# MCU089B_XDS110_USB_Power.net
KiCad netlist of a schematic drawn in Altium Designer
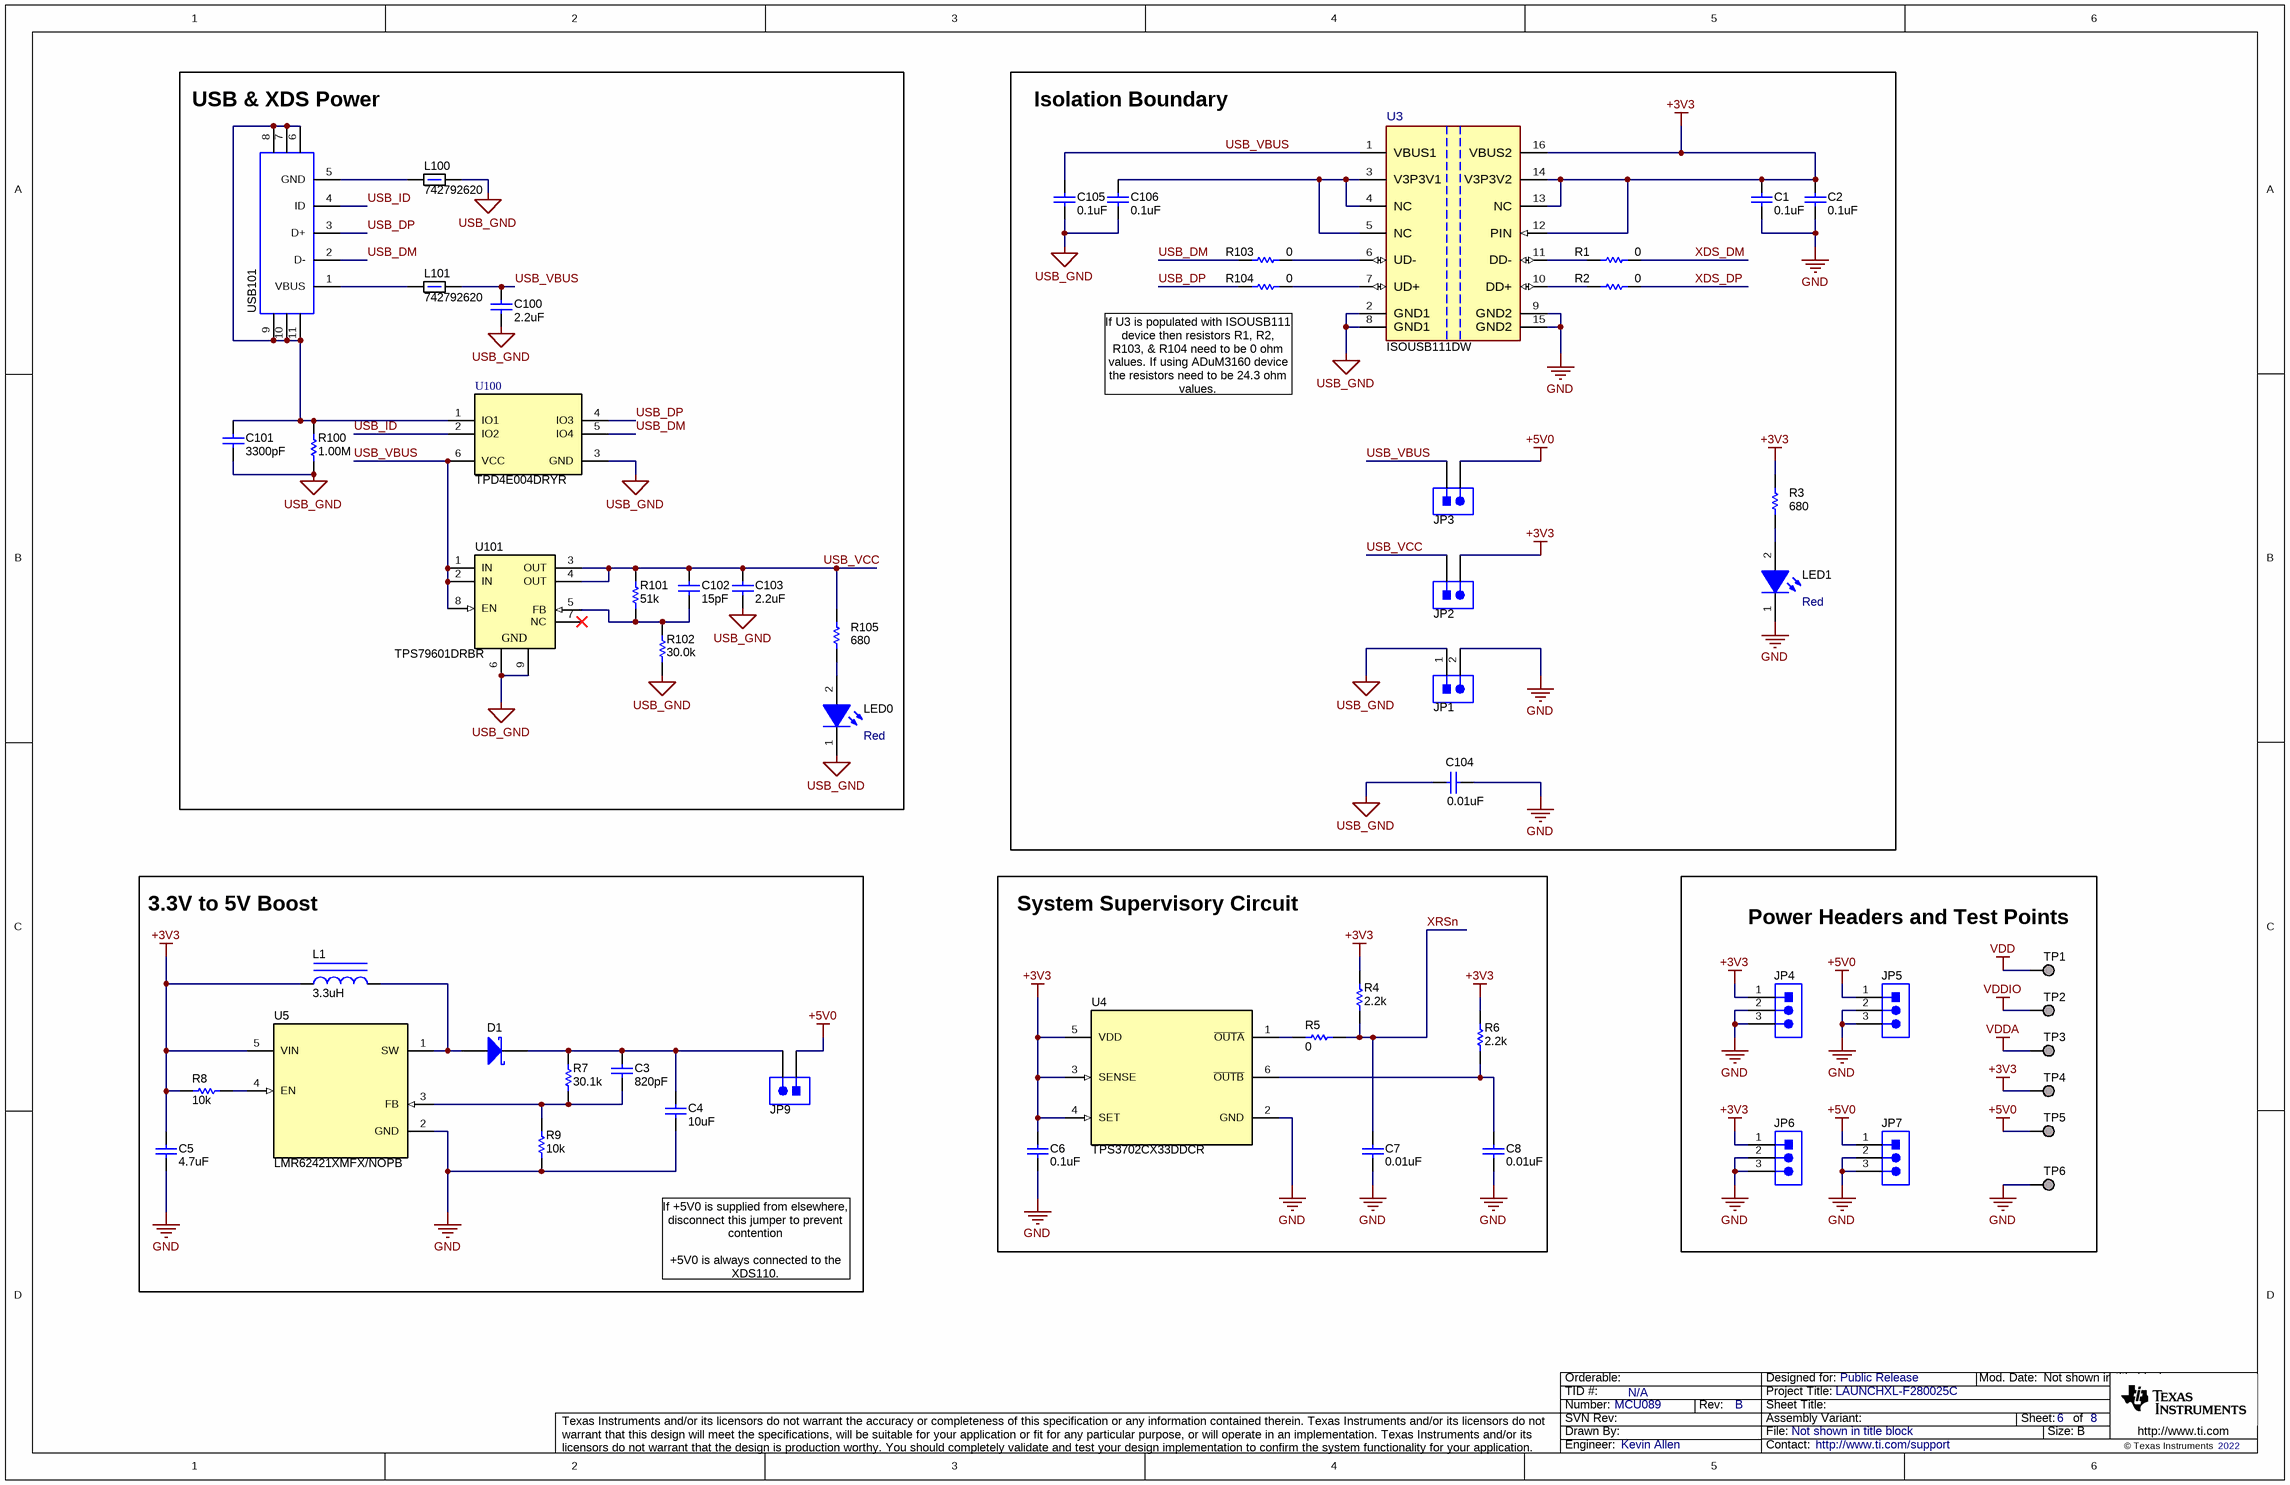
[diagram p0: MCU089B_XDS110_USB_Power.SchDoc]

(export (version "E")
  (design (tool "Eeschema 10.0.6"))
  (components
    (comp (ref "C1")
      (value "GRM155R71A104KA01D")
      (footprint "0402")
      (description "CAP, CERM, 0.1 uF, 10 V, +/- 10%, X7R, 0402")
      (fields
        (field (name "VALUEDISPLAYED") "0.1uF")
        (field (name "MANUFACTURER") "MuRata")
        (field (name "PUBLISHER") "Texas Instruments")
      )
      (libsource (lib "Altium Vault - TI") (part "Capacitor"))
    )
    (comp (ref "C2")
      (value "GRM155R71A104KA01D")
      (footprint "0402")
      (description "CAP, CERM, 0.1 uF, 10 V, +/- 10%, X7R, 0402")
      (fields
        (field (name "VALUEDISPLAYED") "0.1uF")
        (field (name "MANUFACTURER") "MuRata")
        (field (name "PUBLISHER") "Texas Instruments")
      )
      (libsource (lib "Altium Vault - TI") (part "Capacitor"))
    )
    (comp (ref "C3")
      (value "GRM1555C1E821JA01D")
      (footprint "0402")
      (description "CAP, CERM, 820 pF, 25 V, +/- 5%, C0G/NP0, 0402")
      (fields
        (field (name "MANUFACTURER") "MuRata")
        (field (name "VALUEDISPLAYED") "820pF")
        (field (name "PUBLISHER") "Texas Instruments")
      )
      (libsource (lib "Altium Vault - TI") (part "Capacitor"))
    )
    (comp (ref "C4")
      (value "885012209028")
      (footprint "1210_220")
      (description "CAP, CERM, 10 uF, 25 V,+/- 10%, X7R, 1210")
      (fields
        (field (name "VALUEDISPLAYED") "10uF")
        (field (name "MANUFACTURER") "Wurth Elektronik")
        (field (name "PUBLISHER") "Texas Instruments")
      )
      (libsource (lib "Altium Vault - TI") (part "Capacitor"))
    )
    (comp (ref "C5")
      (value "885012105008")
      (footprint "0402")
      (description "CAP, CERM, 4.7 uF, 6.3 V, +/- 20%, X5R, 0402")
      (fields
        (field (name "VALUEDISPLAYED") "4.7uF")
        (field (name "MANUFACTURER") "Wurth Elektronik")
        (field (name "PUBLISHER") "Texas Instruments")
      )
      (libsource (lib "Altium Vault - TI") (part "Capacitor"))
    )
    (comp (ref "C6")
      (value "GRM155R71A104KA01D")
      (footprint "0402")
      (description "CAP, CERM, 0.1 uF, 10 V, +/- 10%, X7R, 0402")
      (fields
        (field (name "VALUEDISPLAYED") "0.1uF")
        (field (name "MANUFACTURER") "MuRata")
        (field (name "PUBLISHER") "Texas Instruments")
      )
      (libsource (lib "Altium Vault - TI") (part "Capacitor"))
    )
    (comp (ref "C7")
      (value "GRM155R71E103KA01D")
      (footprint "0402")
      (description "CAP, CERM, 0.01 uF, 25 V, +/- 10%, X7R, 0402")
      (fields
        (field (name "VALUEDISPLAYED") "0.01uF")
        (field (name "MANUFACTURER") "MuRata")
        (field (name "PUBLISHER") "Texas Instruments")
      )
      (libsource (lib "Altium Vault - TI") (part "Capacitor"))
    )
    (comp (ref "C8")
      (value "GRM155R71E103KA01D")
      (footprint "0402")
      (description "CAP, CERM, 0.01 uF, 25 V, +/- 10%, X7R, 0402")
      (fields
        (field (name "VALUEDISPLAYED") "0.01uF")
        (field (name "MANUFACTURER") "MuRata")
        (field (name "PUBLISHER") "Texas Instruments")
      )
      (libsource (lib "Altium Vault - TI") (part "Capacitor"))
    )
    (comp (ref "C100")
      (value "GRM155R60J225KE95D")
      (footprint "0402")
      (description "CAP, CERM, 2.2 uF, 6.3 V, +/- 10%, X5R, 0402")
      (fields
        (field (name "VALUEDISPLAYED") "2.2uF")
        (field (name "MANUFACTURER") "MuRata")
        (field (name "PUBLISHER") "Texas Instruments")
      )
      (libsource (lib "Altium Vault - TI") (part "Capacitor"))
    )
    (comp (ref "C101")
      (value "GRM155R71H332KA01D")
      (footprint "0402")
      (description "CAP, CERM, 3300 pF, 50 V, +/- 10%, X7R, 0402")
      (fields
        (field (name "VALUEDISPLAYED") "3300pF")
        (field (name "MANUFACTURER") "MuRata")
        (field (name "PUBLISHER") "Texas Instruments")
      )
      (libsource (lib "Altium Vault - TI") (part "Capacitor"))
    )
    (comp (ref "C102")
      (value "885012005056")
      (footprint "0402")
      (description "CAP, CERM, 15 pF, 50 V, +/- 5%, C0G/NP0, 0402")
      (fields
        (field (name "VALUEDISPLAYED") "15pF")
        (field (name "MANUFACTURER") "Wurth Elektronik")
        (field (name "PUBLISHER") "Texas Instruments")
      )
      (libsource (lib "Altium Vault - TI") (part "Capacitor"))
    )
    (comp (ref "C103")
      (value "GRM155R60J225KE95D")
      (footprint "0402")
      (description "CAP, CERM, 2.2 uF, 6.3 V, +/- 10%, X5R, 0402")
      (fields
        (field (name "VALUEDISPLAYED") "2.2uF")
        (field (name "MANUFACTURER") "MuRata")
        (field (name "PUBLISHER") "Texas Instruments")
      )
      (libsource (lib "Altium Vault - TI") (part "Capacitor"))
    )
    (comp (ref "C104")
      (value "1812SC103KAT1A")
      (footprint "1812")
      (description "CAP, CERM, 0.01 uF, 1500 V, +/- 10%, X7R, 1812")
      (fields
        (field (name "MANUFACTURER") "AVX")
        (field (name "VALUEDISPLAYED") "0.01uF")
        (field (name "PUBLISHER") "Texas Instruments")
      )
      (libsource (lib "Altium Vault - TI") (part "Capacitor"))
    )
    (comp (ref "C105")
      (value "GRM155R71A104KA01D")
      (footprint "0402")
      (description "CAP, CERM, 0.1 uF, 10 V, +/- 10%, X7R, 0402")
      (fields
        (field (name "VALUEDISPLAYED") "0.1uF")
        (field (name "MANUFACTURER") "MuRata")
        (field (name "PUBLISHER") "Texas Instruments")
      )
      (libsource (lib "Altium Vault - TI") (part "Capacitor"))
    )
    (comp (ref "C106")
      (value "GRM155R71A104KA01D")
      (footprint "0402")
      (description "CAP, CERM, 0.1 uF, 10 V, +/- 10%, X7R, 0402")
      (fields
        (field (name "VALUEDISPLAYED") "0.1uF")
        (field (name "MANUFACTURER") "MuRata")
        (field (name "PUBLISHER") "Texas Instruments")
      )
      (libsource (lib "Altium Vault - TI") (part "Capacitor"))
    )
    (comp (ref "D1")
      (value "1N5819HW-7-F")
      (footprint "SOD-123")
      (description "Diode, Schottky, 40 V, 1 A, SOD-123")
      (fields (field (name "MANUFACTURER") "Diodes Inc."))
      (libsource (lib "Altium Vault - TI") (part "DIODE_SCHOTTKY"))
    )
    (comp (ref "JP1")
      (value "61300211121")
      (footprint "WURTH_61300211121")
      (description "Header, 2.54 mm, 2x1, Gold, TH")
      (fields (field (name "MANUFACTURER") "Wurth Elektronik") (field (name "PUBLISHER") "Texas Instruments"))
      (libsource (lib "Altium Vault - TI") (part "Header_2x1"))
    )
    (comp (ref "JP2")
      (value "61300211121")
      (footprint "WURTH_61300211121")
      (description "Header, 2.54 mm, 2x1, Gold, TH")
      (fields (field (name "MANUFACTURER") "Wurth Elektronik") (field (name "PUBLISHER") "Texas Instruments"))
      (libsource (lib "") (part "CMP-0054794-1_1"))
    )
    (comp (ref "JP3")
      (value "61300211121")
      (footprint "WURTH_61300211121")
      (description "Header, 2.54 mm, 2x1, Gold, TH")
      (fields (field (name "MANUFACTURER") "Wurth Elektronik") (field (name "PUBLISHER") "Texas Instruments"))
      (libsource (lib "") (part "CMP-0054794-1_1"))
    )
    (comp (ref "JP4")
      (value "61300311121")
      (footprint "WURTH_61300311121")
      (description "Header, 2.54 mm, 3x1, Gold, TH")
      (fields (field (name "MANUFACTURER") "Wurth Elektronik") (field (name "PUBLISHER") "Texas Instruments"))
      (libsource (lib "Altium Vault - TI") (part "Header_3x1"))
    )
    (comp (ref "JP5")
      (value "61300311121")
      (footprint "WURTH_61300311121")
      (description "Header, 2.54 mm, 3x1, Gold, TH")
      (fields (field (name "MANUFACTURER") "Wurth Elektronik") (field (name "PUBLISHER") "Texas Instruments"))
      (libsource (lib "Altium Vault - TI") (part "Header_3x1"))
    )
    (comp (ref "JP6")
      (value "61300311121")
      (footprint "WURTH_61300311121")
      (description "Header, 2.54 mm, 3x1, Gold, TH")
      (fields (field (name "MANUFACTURER") "Wurth Elektronik") (field (name "PUBLISHER") "Texas Instruments"))
      (libsource (lib "Altium Vault - TI") (part "Header_3x1"))
    )
    (comp (ref "JP7")
      (value "61300311121")
      (footprint "WURTH_61300311121")
      (description "Header, 2.54 mm, 3x1, Gold, TH")
      (fields (field (name "MANUFACTURER") "Wurth Elektronik") (field (name "PUBLISHER") "Texas Instruments"))
      (libsource (lib "Altium Vault - TI") (part "Header_3x1"))
    )
    (comp (ref "JP9")
      (value "61300211121")
      (footprint "WURTH_61300211121")
      (description "Header, 2.54 mm, 2x1, Gold, TH")
      (fields (field (name "MANUFACTURER") "Wurth Elektronik") (field (name "PUBLISHER") "Texas Instruments"))
      (libsource (lib "Altium Vault - TI") (part "CMP-0054794-1"))
    )
    (comp (ref "L1")
      (value "744025003")
      (footprint "WE-TPC_2828")
      (description "Inductor, Shielded Drum Core, Ferrite, 3.3 uH, 1.5 A, 0.085 ohm, SMD")
      (fields
        (field (name "VALUEDISPLAYED") "3.3uH")
        (field (name "MANUFACTURER") "Wurth Elektronik")
        (field (name "PUBLISHER") "Texas Instruments")
      )
      (libsource (lib "Altium Vault - TI") (part "Inductor_Iron"))
    )
    (comp (ref "L100")
      (value "742792620")
      (footprint "0603")
      (description "Ferrite Bead, 100 ohm @ 100 MHz, 0.5 A, 0603")
      (fields (field (name "MANUFACTURER") "Wurth Elektronik") (field (name "PUBLISHER") "Texas Instruments"))
      (libsource (lib "Altium Vault - TI") (part "Ferrite_Bead"))
    )
    (comp (ref "L101")
      (value "742792620")
      (footprint "0603")
      (description "Ferrite Bead, 100 ohm @ 100 MHz, 0.5 A, 0603")
      (fields (field (name "MANUFACTURER") "Wurth Elektronik") (field (name "PUBLISHER") "Texas Instruments"))
      (libsource (lib "Altium Vault - TI") (part "Ferrite_Bead"))
    )
    (comp (ref "LED0")
      (value "Red")
      (footprint "WL-SMCW_RED_0805")
      (description "LED, Red, SMD")
      (fields (field (name "MANUFACTURER") "Wurth Elektronik") (field (name "PARTNUMBER") "150080SS75000"))
      (libsource (lib "Altium Vault - TI") (part "LED_A2_K1"))
    )
    (comp (ref "LED1")
      (value "Red")
      (footprint "WL-SMCW_RED_0805")
      (description "LED, Red, SMD")
      (fields (field (name "MANUFACTURER") "Wurth Elektronik") (field (name "PARTNUMBER") "150080SS75000"))
      (libsource (lib "Altium Vault - TI") (part "LED_A2_K1"))
    )
    (comp (ref "R1")
      (value "RC0402JR-070RL")
      (footprint "0402")
      (description "RES, 0, 5%, 0.063 W, 0402")
      (fields
        (field (name "MANUFACTURER") "Yageo America")
        (field (name "VALUEDISPLAYED") "0")
        (field (name "PUBLISHER") "Texas Instruments")
      )
      (libsource (lib "Altium Vault - TI") (part "Resistor"))
    )
    (comp (ref "R2")
      (value "RC0402JR-070RL")
      (footprint "0402")
      (description "RES, 0, 5%, 0.063 W, 0402")
      (fields
        (field (name "MANUFACTURER") "Yageo America")
        (field (name "VALUEDISPLAYED") "0")
        (field (name "PUBLISHER") "Texas Instruments")
      )
      (libsource (lib "Altium Vault - TI") (part "Resistor"))
    )
    (comp (ref "R3")
      (value "CRCW0402680RJNED")
      (footprint "0402")
      (description "RES, 680, 5%, 0.063 W, AEC-Q200 Grade 0, 0402")
      (fields (field (name "MANUFACTURER") "Vishay-Dale") (field (name "VALUEDISPLAYED") "680"))
      (libsource (lib "Altium Vault - TI") (part "CMP-0026962-3"))
    )
    (comp (ref "R4")
      (value "CRCW04022K20JNED")
      (footprint "0402")
      (description "RES, 2.2 k, 5%, 0.063 W, AEC-Q200 Grade 0, 0402")
      (fields (field (name "VALUEDISPLAYED") "2.2k") (field (name "MANUFACTURER") "Vishay-Dale"))
      (libsource (lib "Altium Vault - TI") (part "Resistor"))
    )
    (comp (ref "R5")
      (value "CRCW04020000Z0ED")
      (footprint "0402")
      (description "RES, 0, 5%, 0.063 W, AEC-Q200 Grade 0, 0402")
      (fields (field (name "VALUEDISPLAYED") "0") (field (name "MANUFACTURER") "Vishay-Dale"))
      (libsource (lib "Altium Vault - TI") (part "Resistor"))
    )
    (comp (ref "R6")
      (value "CRCW06032K20JNEA")
      (footprint "0603")
      (description "RES, 2.2 k, 5%, 0.1 W, AEC-Q200 Grade 0, 0603")
      (fields (field (name "VALUEDISPLAYED") "2.2k") (field (name "MANUFACTURER") "Vishay-Dale"))
      (libsource (lib "Altium Vault - TI") (part "Resistor"))
    )
    (comp (ref "R7")
      (value "RC0402FR-0730K1L")
      (footprint "0402")
      (description "RES, 30.1 k, 1%, 0.063 W, 0402")
      (fields
        (field (name "VALUEDISPLAYED") "30.1k")
        (field (name "MANUFACTURER") "Yageo America")
        (field (name "PUBLISHER") "Texas Instruments")
      )
      (libsource (lib "Altium Vault - TI") (part "Resistor"))
    )
    (comp (ref "R8")
      (value "CRCW040210K0JNED")
      (footprint "0402")
      (description "RES, 10 k, 5%, 0.063 W, AEC-Q200 Grade 0, 0402")
      (fields (field (name "VALUEDISPLAYED") "10k") (field (name "MANUFACTURER") "Vishay-Dale"))
      (libsource (lib "Altium Vault - TI") (part "Resistor"))
    )
    (comp (ref "R9")
      (value "CRCW040210K0JNED")
      (footprint "0402")
      (description "RES, 10 k, 5%, 0.063 W, AEC-Q200 Grade 0, 0402")
      (fields (field (name "VALUEDISPLAYED") "10k") (field (name "MANUFACTURER") "Vishay-Dale"))
      (libsource (lib "Altium Vault - TI") (part "Resistor"))
    )
    (comp (ref "R100")
      (value "CRCW04021M00FKED")
      (footprint "0402")
      (description "RES, 1.00 M, 1%, 0.063 W, AEC-Q200 Grade 0, 0402")
      (fields (field (name "VALUEDISPLAYED") "1.00M") (field (name "MANUFACTURER") "Vishay-Dale"))
      (libsource (lib "Altium Vault - TI") (part "Resistor"))
    )
    (comp (ref "R101")
      (value "CRCW040251K0FKED")
      (footprint "0402")
      (description "RES Thick Film SMD 51kΩ 1% 1/16W 0402 100ppm/K")
      (fields (field (name "MANUFACTURER") "Vishay") (field (name "VALUEDISPLAYED") "51k"))
      (libsource (lib "Altium Vault - TI") (part "Resistor"))
    )
    (comp (ref "R102")
      (value "CRCW040230K0FKED")
      (footprint "0402")
      (description "RES, 30.0 k, 1%, 0.063 W, AEC-Q200 Grade 0, 0402")
      (fields (field (name "MANUFACTURER") "Vishay-Dale") (field (name "VALUEDISPLAYED") "30.0k"))
      (libsource (lib "Altium Vault - TI") (part "Resistor"))
    )
    (comp (ref "R103")
      (value "RC0402JR-070RL")
      (footprint "0402")
      (description "RES, 0, 5%, 0.063 W, 0402")
      (fields
        (field (name "MANUFACTURER") "Yageo America")
        (field (name "VALUEDISPLAYED") "0")
        (field (name "PUBLISHER") "Texas Instruments")
      )
      (libsource (lib "Altium Vault - TI") (part "Resistor"))
    )
    (comp (ref "R104")
      (value "RC0402JR-070RL")
      (footprint "0402")
      (description "RES, 0, 5%, 0.063 W, 0402")
      (fields
        (field (name "MANUFACTURER") "Yageo America")
        (field (name "VALUEDISPLAYED") "0")
        (field (name "PUBLISHER") "Texas Instruments")
      )
      (libsource (lib "Altium Vault - TI") (part "Resistor"))
    )
    (comp (ref "R105")
      (value "CRCW0402680RJNED")
      (footprint "0402")
      (description "RES, 680, 5%, 0.063 W, AEC-Q200 Grade 0, 0402")
      (fields (field (name "MANUFACTURER") "Vishay-Dale") (field (name "VALUEDISPLAYED") "680"))
      (libsource (lib "Altium Vault - TI") (part "CMP-0026962-3"))
    )
    (comp (ref "TP1")
      (value "TESTPOINT")
      (footprint "TP_50MIL-25MILHOLE")
      (description "TEST POINT.  No entry in BOM.")
      (libsource (lib "Altium Vault - TI") (part "TESTPOINT"))
    )
    (comp (ref "TP2")
      (value "TESTPOINT")
      (footprint "TP_50MIL-25MILHOLE")
      (description "TEST POINT.  No entry in BOM.")
      (libsource (lib "Altium Vault - TI") (part "TESTPOINT"))
    )
    (comp (ref "TP3")
      (value "TESTPOINT")
      (footprint "TP_50MIL-25MILHOLE")
      (description "TEST POINT.  No entry in BOM.")
      (libsource (lib "Altium Vault - TI") (part "TESTPOINT"))
    )
    (comp (ref "TP4")
      (value "TESTPOINT")
      (footprint "TP_50MIL-25MILHOLE")
      (description "TEST POINT.  No entry in BOM.")
      (libsource (lib "Altium Vault - TI") (part "TESTPOINT"))
    )
    (comp (ref "TP5")
      (value "TESTPOINT")
      (footprint "TP_50MIL-25MILHOLE")
      (description "TEST POINT.  No entry in BOM.")
      (libsource (lib "Altium Vault - TI") (part "TESTPOINT"))
    )
    (comp (ref "TP6")
      (value "TESTPOINT")
      (footprint "TP_50MIL-25MILHOLE")
      (description "TEST POINT.  No entry in BOM.")
      (libsource (lib "Altium Vault - TI") (part "TESTPOINT"))
    )
    (comp (ref "U3")
      (value "ISOUSB111DW")
      (footprint "DW0016B-MFG")
      (description "Full/Low Speed Isolated USB Repeater, SOIC16-Wide")
      (fields (field (name "MANUFACTURER") "Texas Instruments") (field (name "PARTNUMBER") "ISOUSB111DW"))
      (libsource (lib "Altium Vault - TI") (part "SYM-ISOUSB111DW"))
    )
    (comp (ref "U4")
      (value "TPS3702CX33DDCR")
      (footprint "DDC0006A_N")
      (description "High-Accuracy, Fixed-Threshold OV/UV Monitor, DDC0006A (SOT-23-T-6)")
      (fields
        (field (name "ALTERNATE PARTNUMBER") "TPS3702CX33DDCT")
        (field (name "MANUFACTURER") "Texas Instruments")
        (field (name "PUBLISHER") "Texas Instruments")
      )
      (libsource (lib "Altium Vault - TI") (part "TPS3702"))
    )
    (comp (ref "U5")
      (value "LMR62421XMFX/NOPB")
      (footprint "DBV0005A_N")
      (description "SIMPLE SWITCHER 2.7V to 5.5V, 2.1A Step-Up Regulator in SOT-23, DBV0005A (SOT-23-5)")
      (fields
        (field (name "ALTERNATE PARTNUMBER") "LMR62421XMFE/NOPB")
        (field (name "MANUFACTURER") "Texas Instruments")
        (field (name "PUBLISHER") "Texas Instruments")
      )
      (libsource (lib "Altium Vault - TI") (part "LMR62421DBV"))
    )
    (comp (ref "U100")
      (value "TPD4E004DRYR")
      (footprint "DRY0006A")
      (description "4-Channel ESD Protection Array for High-Speed Data Interfaces, DRY0006A (USON-6)")
      (fields (field (name "MANUFACTURER") "Texas Instruments") (field (name "PARTNUMBER") "TPD4E004DRYR"))
      (libsource (lib "Altium Vault - TI") (part "TI-TPD4E004-SON_DRY-6"))
    )
    (comp (ref "U101")
      (value "TPS79601DRBR")
      (footprint "DRB0008B")
      (fields (field (name "MANUFACTURER") "Texas Instruments"))
      (libsource (lib "Altium Vault - TI") (part "CMP-0036402-3"))
    )
    (comp (ref "USB101")
      (value "1051640001")
      (footprint "Molex_1051640001")
      (description "Receptacle, USB 2.0, Micro B, 5 Position, R/A, SMT")
      (fields (field (name "MANUFACTURER") "Molex") (field (name "PUBLISHER") "Texas Instruments"))
      (libsource (lib "Altium Vault - TI") (part "CONN_USB_MicroMini_6Shld"))
    )
  )
  (nets
    (net (code "1") (name "+3V3") (class "Default")
      (node (ref "C1") (pin "2") (pinfunction "2_2") (pintype "passive"))
      (node (ref "C2") (pin "2") (pinfunction "2_2") (pintype "passive"))
      (node (ref "C5") (pin "1") (pinfunction "1_1") (pintype "passive"))
      (node (ref "C6") (pin "2") (pinfunction "2_2") (pintype "passive"))
      (node (ref "JP2") (pin "2") (pinfunction "2_2") (pintype "passive"))
      (node (ref "JP4") (pin "1") (pinfunction "1_1") (pintype "passive"))
      (node (ref "JP6") (pin "1") (pinfunction "1_1") (pintype "passive"))
      (node (ref "L1") (pin "1") (pinfunction "1_1") (pintype "passive"))
      (node (ref "R3") (pin "2") (pinfunction "2_2") (pintype "passive"))
      (node (ref "R4") (pin "2") (pinfunction "2_2") (pintype "passive"))
      (node (ref "R6") (pin "2") (pinfunction "2_2") (pintype "passive"))
      (node (ref "R8") (pin "2") (pinfunction "2_2") (pintype "passive"))
      (node (ref "TP4") (pin "1") (pintype "passive"))
      (node (ref "U3") (pin "12") (pinfunction "PIN_12") (pintype "input"))
      (node (ref "U3") (pin "13") (pinfunction "NC_13") (pintype "passive"))
      (node (ref "U3") (pin "14") (pinfunction "V3P3V2_14") (pintype "power_in"))
      (node (ref "U3") (pin "16") (pinfunction "VBUS2_16") (pintype "power_in"))
      (node (ref "U4") (pin "3") (pinfunction "SENSE_3") (pintype "input"))
      (node (ref "U4") (pin "4") (pinfunction "SET_4") (pintype "input"))
      (node (ref "U4") (pin "5") (pinfunction "VDD_5") (pintype "power_in"))
      (node (ref "U5") (pin "5") (pinfunction "VIN_5") (pintype "power_in"))
    )
    (net (code "2") (name "+5V0") (class "Default")
      (node (ref "JP3") (pin "2") (pinfunction "2_2") (pintype "passive"))
      (node (ref "JP5") (pin "1") (pinfunction "1_1") (pintype "passive"))
      (node (ref "JP7") (pin "1") (pinfunction "1_1") (pintype "passive"))
      (node (ref "JP9") (pin "1") (pinfunction "1_1") (pintype "passive"))
      (node (ref "TP5") (pin "1") (pintype "passive"))
    )
    (net (code "3") (name "/USB_DM") (class "Default")
      (node (ref "R103") (pin "1") (pinfunction "1_1") (pintype "passive"))
      (node (ref "U100") (pin "5") (pinfunction "IO4_5") (pintype "passive"))
      (node (ref "USB101") (pin "2") (pinfunction "D-_2") (pintype "passive"))
    )
    (net (code "4") (name "/USB_DP") (class "Default")
      (node (ref "R104") (pin "1") (pinfunction "1_1") (pintype "passive"))
      (node (ref "U100") (pin "4") (pinfunction "IO3_4") (pintype "passive"))
      (node (ref "USB101") (pin "3") (pinfunction "D+_3") (pintype "passive"))
    )
    (net (code "5") (name "/USB_ID") (class "Default")
      (node (ref "U100") (pin "2") (pinfunction "IO2_2") (pintype "passive"))
      (node (ref "USB101") (pin "4") (pinfunction "ID_4") (pintype "passive"))
    )
    (net (code "6") (name "/USB_VBUS") (class "Default")
      (node (ref "C100") (pin "1") (pinfunction "1_1") (pintype "passive"))
      (node (ref "C105") (pin "2") (pinfunction "2_2") (pintype "passive"))
      (node (ref "JP3") (pin "1") (pinfunction "1_1") (pintype "passive"))
      (node (ref "L101") (pin "2") (pinfunction "2_2") (pintype "passive"))
      (node (ref "U100") (pin "6") (pinfunction "VCC_6") (pintype "power_in"))
      (node (ref "U101") (pin "1") (pinfunction "IN_1") (pintype "power_in"))
      (node (ref "U101") (pin "2") (pinfunction "IN_2") (pintype "power_in"))
      (node (ref "U101") (pin "8") (pinfunction "EN_8") (pintype "input"))
      (node (ref "U3") (pin "1") (pinfunction "VBUS1_1") (pintype "power_in"))
    )
    (net (code "7") (name "/USB_VCC") (class "Default")
      (node (ref "C102") (pin "1") (pinfunction "1_1") (pintype "passive"))
      (node (ref "C103") (pin "1") (pinfunction "1_1") (pintype "passive"))
      (node (ref "JP2") (pin "1") (pinfunction "1_1") (pintype "passive"))
      (node (ref "R101") (pin "2") (pinfunction "2_2") (pintype "passive"))
      (node (ref "R105") (pin "2") (pinfunction "2_2") (pintype "passive"))
      (node (ref "U101") (pin "3") (pinfunction "OUT_3") (pintype "power_in"))
      (node (ref "U101") (pin "4") (pinfunction "OUT_4") (pintype "power_in"))
    )
    (net (code "8") (name "/XDS_DM") (class "Default")
      (node (ref "R1") (pin "2") (pinfunction "2_2") (pintype "passive"))
    )
    (net (code "9") (name "/XDS_DP") (class "Default")
      (node (ref "R2") (pin "2") (pinfunction "2_2") (pintype "passive"))
    )
    (net (code "10") (name "/XRSn") (class "Default")
      (node (ref "C7") (pin "1") (pinfunction "1_1") (pintype "passive"))
      (node (ref "R4") (pin "1") (pinfunction "1_1") (pintype "passive"))
      (node (ref "R5") (pin "2") (pinfunction "2_2") (pintype "passive"))
    )
    (net (code "11") (name "GND") (class "Default")
      (node (ref "C1") (pin "1") (pinfunction "1_1") (pintype "passive"))
      (node (ref "C104") (pin "1") (pinfunction "1_1") (pintype "passive"))
      (node (ref "C2") (pin "1") (pinfunction "1_1") (pintype "passive"))
      (node (ref "C4") (pin "2") (pinfunction "2_2") (pintype "passive"))
      (node (ref "C5") (pin "2") (pinfunction "2_2") (pintype "passive"))
      (node (ref "C6") (pin "1") (pinfunction "1_1") (pintype "passive"))
      (node (ref "C7") (pin "2") (pinfunction "2_2") (pintype "passive"))
      (node (ref "C8") (pin "2") (pinfunction "2_2") (pintype "passive"))
      (node (ref "JP1") (pin "2") (pinfunction "2_2") (pintype "passive"))
      (node (ref "JP4") (pin "2") (pinfunction "2_2") (pintype "passive"))
      (node (ref "JP4") (pin "3") (pinfunction "3_3") (pintype "passive"))
      (node (ref "JP5") (pin "2") (pinfunction "2_2") (pintype "passive"))
      (node (ref "JP5") (pin "3") (pinfunction "3_3") (pintype "passive"))
      (node (ref "JP6") (pin "2") (pinfunction "2_2") (pintype "passive"))
      (node (ref "JP6") (pin "3") (pinfunction "3_3") (pintype "passive"))
      (node (ref "JP7") (pin "2") (pinfunction "2_2") (pintype "passive"))
      (node (ref "JP7") (pin "3") (pinfunction "3_3") (pintype "passive"))
      (node (ref "LED1") (pin "1") (pinfunction "K_1") (pintype "passive"))
      (node (ref "R9") (pin "1") (pinfunction "1_1") (pintype "passive"))
      (node (ref "TP6") (pin "1") (pintype "passive"))
      (node (ref "U3") (pin "15") (pinfunction "GND2_15") (pintype "power_in"))
      (node (ref "U3") (pin "9") (pinfunction "GND2_9") (pintype "power_in"))
      (node (ref "U4") (pin "2") (pinfunction "GND_2") (pintype "power_in"))
      (node (ref "U5") (pin "2") (pinfunction "GND_2") (pintype "power_in"))
    )
    (net (code "12") (name "Net-(D1-A)") (class "Default")
      (node (ref "D1") (pin "2") (pinfunction "A_2") (pintype "passive"))
      (node (ref "L1") (pin "2") (pinfunction "2_2") (pintype "passive"))
      (node (ref "U5") (pin "1") (pinfunction "SW_1") (pintype "power_in"))
    )
    (net (code "13") (name "Net-(D1-K)") (class "Default")
      (node (ref "C3") (pin "1") (pinfunction "1_1") (pintype "passive"))
      (node (ref "C4") (pin "1") (pinfunction "1_1") (pintype "passive"))
      (node (ref "D1") (pin "1") (pinfunction "K_1") (pintype "passive"))
      (node (ref "JP9") (pin "2") (pinfunction "2_2") (pintype "passive"))
      (node (ref "R7") (pin "2") (pinfunction "2_2") (pintype "passive"))
    )
    (net (code "14") (name "Net-(LED0-A)") (class "Default")
      (node (ref "LED0") (pin "2") (pinfunction "A_2") (pintype "passive"))
      (node (ref "R105") (pin "1") (pinfunction "1_1") (pintype "passive"))
    )
    (net (code "15") (name "Net-(LED1-A)") (class "Default")
      (node (ref "LED1") (pin "2") (pinfunction "A_2") (pintype "passive"))
      (node (ref "R3") (pin "1") (pinfunction "1_1") (pintype "passive"))
    )
    (net (code "16") (name "Net-(U3-DD+)") (class "Default")
      (node (ref "R2") (pin "1") (pinfunction "1_1") (pintype "passive"))
      (node (ref "U3") (pin "10") (pinfunction "DD+_10") (pintype "bidirectional"))
    )
    (net (code "17") (name "Net-(U3-DD-)") (class "Default")
      (node (ref "R1") (pin "1") (pinfunction "1_1") (pintype "passive"))
      (node (ref "U3") (pin "11") (pinfunction "DD-_11") (pintype "bidirectional"))
    )
    (net (code "18") (name "Net-(U3-UD+)") (class "Default")
      (node (ref "R104") (pin "2") (pinfunction "2_2") (pintype "passive"))
      (node (ref "U3") (pin "7") (pinfunction "UD+_7") (pintype "bidirectional"))
    )
    (net (code "19") (name "Net-(U3-UD-)") (class "Default")
      (node (ref "R103") (pin "2") (pinfunction "2_2") (pintype "passive"))
      (node (ref "U3") (pin "6") (pinfunction "UD-_6") (pintype "bidirectional"))
    )
    (net (code "20") (name "Net-(U3-V3P3V1)") (class "Default")
      (node (ref "C106") (pin "2") (pinfunction "2_2") (pintype "passive"))
      (node (ref "U3") (pin "3") (pinfunction "V3P3V1_3") (pintype "power_in"))
      (node (ref "U3") (pin "4") (pinfunction "NC_4") (pintype "passive"))
      (node (ref "U3") (pin "5") (pinfunction "NC_5") (pintype "passive"))
    )
    (net (code "21") (name "Net-(U4-OUTA)") (class "Default")
      (node (ref "R5") (pin "1") (pinfunction "1_1") (pintype "passive"))
      (node (ref "U4") (pin "1") (pinfunction "OUTA_1") (pintype "open_collector"))
    )
    (net (code "22") (name "Net-(U4-OUTB)") (class "Default")
      (node (ref "C8") (pin "1") (pinfunction "1_1") (pintype "passive"))
      (node (ref "R6") (pin "1") (pinfunction "1_1") (pintype "passive"))
      (node (ref "U4") (pin "6") (pinfunction "OUTB_6") (pintype "open_collector"))
    )
    (net (code "23") (name "Net-(U5-EN)") (class "Default")
      (node (ref "R8") (pin "1") (pinfunction "1_1") (pintype "passive"))
      (node (ref "U5") (pin "4") (pinfunction "EN_4") (pintype "input"))
    )
    (net (code "24") (name "Net-(U5-FB)") (class "Default")
      (node (ref "C3") (pin "2") (pinfunction "2_2") (pintype "passive"))
      (node (ref "R7") (pin "1") (pinfunction "1_1") (pintype "passive"))
      (node (ref "R9") (pin "2") (pinfunction "2_2") (pintype "passive"))
      (node (ref "U5") (pin "3") (pinfunction "FB_3") (pintype "input"))
    )
    (net (code "25") (name "Net-(U100-IO1)") (class "Default")
      (node (ref "C101") (pin "1") (pinfunction "1_1") (pintype "passive"))
      (node (ref "R100") (pin "2") (pinfunction "2_2") (pintype "passive"))
      (node (ref "U100") (pin "1") (pinfunction "IO1_1") (pintype "passive"))
      (node (ref "USB101") (pin "10") (pinfunction "10_10") (pintype "passive"))
      (node (ref "USB101") (pin "11") (pinfunction "11_11") (pintype "passive"))
      (node (ref "USB101") (pin "6") (pinfunction "6_6") (pintype "passive"))
      (node (ref "USB101") (pin "7") (pinfunction "7_7") (pintype "passive"))
      (node (ref "USB101") (pin "8") (pinfunction "8_8") (pintype "passive"))
      (node (ref "USB101") (pin "9") (pinfunction "9_9") (pintype "passive"))
    )
    (net (code "26") (name "Net-(U101-FB)") (class "Default")
      (node (ref "C102") (pin "2") (pinfunction "2_2") (pintype "passive"))
      (node (ref "R101") (pin "1") (pinfunction "1_1") (pintype "passive"))
      (node (ref "R102") (pin "2") (pinfunction "2_2") (pintype "passive"))
      (node (ref "U101") (pin "5") (pinfunction "FB_5") (pintype "input"))
    )
    (net (code "27") (name "Net-(USB101-GND)") (class "Default")
      (node (ref "L100") (pin "1") (pinfunction "1_1") (pintype "passive"))
      (node (ref "USB101") (pin "5") (pinfunction "GND_5") (pintype "passive"))
    )
    (net (code "28") (name "Net-(USB101-VBUS)") (class "Default")
      (node (ref "L101") (pin "1") (pinfunction "1_1") (pintype "passive"))
      (node (ref "USB101") (pin "1") (pinfunction "VBUS_1") (pintype "passive"))
    )
    (net (code "29") (name "USB_GND") (class "Default")
      (node (ref "C100") (pin "2") (pinfunction "2_2") (pintype "passive"))
      (node (ref "C101") (pin "2") (pinfunction "2_2") (pintype "passive"))
      (node (ref "C103") (pin "2") (pinfunction "2_2") (pintype "passive"))
      (node (ref "C104") (pin "2") (pinfunction "2_2") (pintype "passive"))
      (node (ref "C105") (pin "1") (pinfunction "1_1") (pintype "passive"))
      (node (ref "C106") (pin "1") (pinfunction "1_1") (pintype "passive"))
      (node (ref "JP1") (pin "1") (pinfunction "1_1") (pintype "passive"))
      (node (ref "L100") (pin "2") (pinfunction "2_2") (pintype "passive"))
      (node (ref "LED0") (pin "1") (pinfunction "K_1") (pintype "passive"))
      (node (ref "R100") (pin "1") (pinfunction "1_1") (pintype "passive"))
      (node (ref "R102") (pin "1") (pinfunction "1_1") (pintype "passive"))
      (node (ref "U100") (pin "3") (pinfunction "GND_3") (pintype "power_in"))
      (node (ref "U101") (pin "6") (pinfunction "GND_6") (pintype "power_in"))
      (node (ref "U101") (pin "9") (pinfunction "GND_9") (pintype "power_in"))
      (node (ref "U3") (pin "2") (pinfunction "GND1_2") (pintype "power_in"))
      (node (ref "U3") (pin "8") (pinfunction "GND1_8") (pintype "power_in"))
    )
    (net (code "30") (name "VDD") (class "Default") (node (ref "TP1") (pin "1") (pintype "passive")))
    (net (code "31") (name "VDDA") (class "Default") (node (ref "TP3") (pin "1") (pintype "passive")))
    (net (code "32") (name "VDDIO") (class "Default") (node (ref "TP2") (pin "1") (pintype "passive")))
    (net (code "33") (name "unconnected-(U101-NC-Pad7)") (class "Default")
      (node (ref "U101") (pin "7") (pinfunction "NC_7") (pintype "passive+no_connect"))
    )
  )
)
